# sch.net
KiCad netlist of a schematic drawn in EAGLE
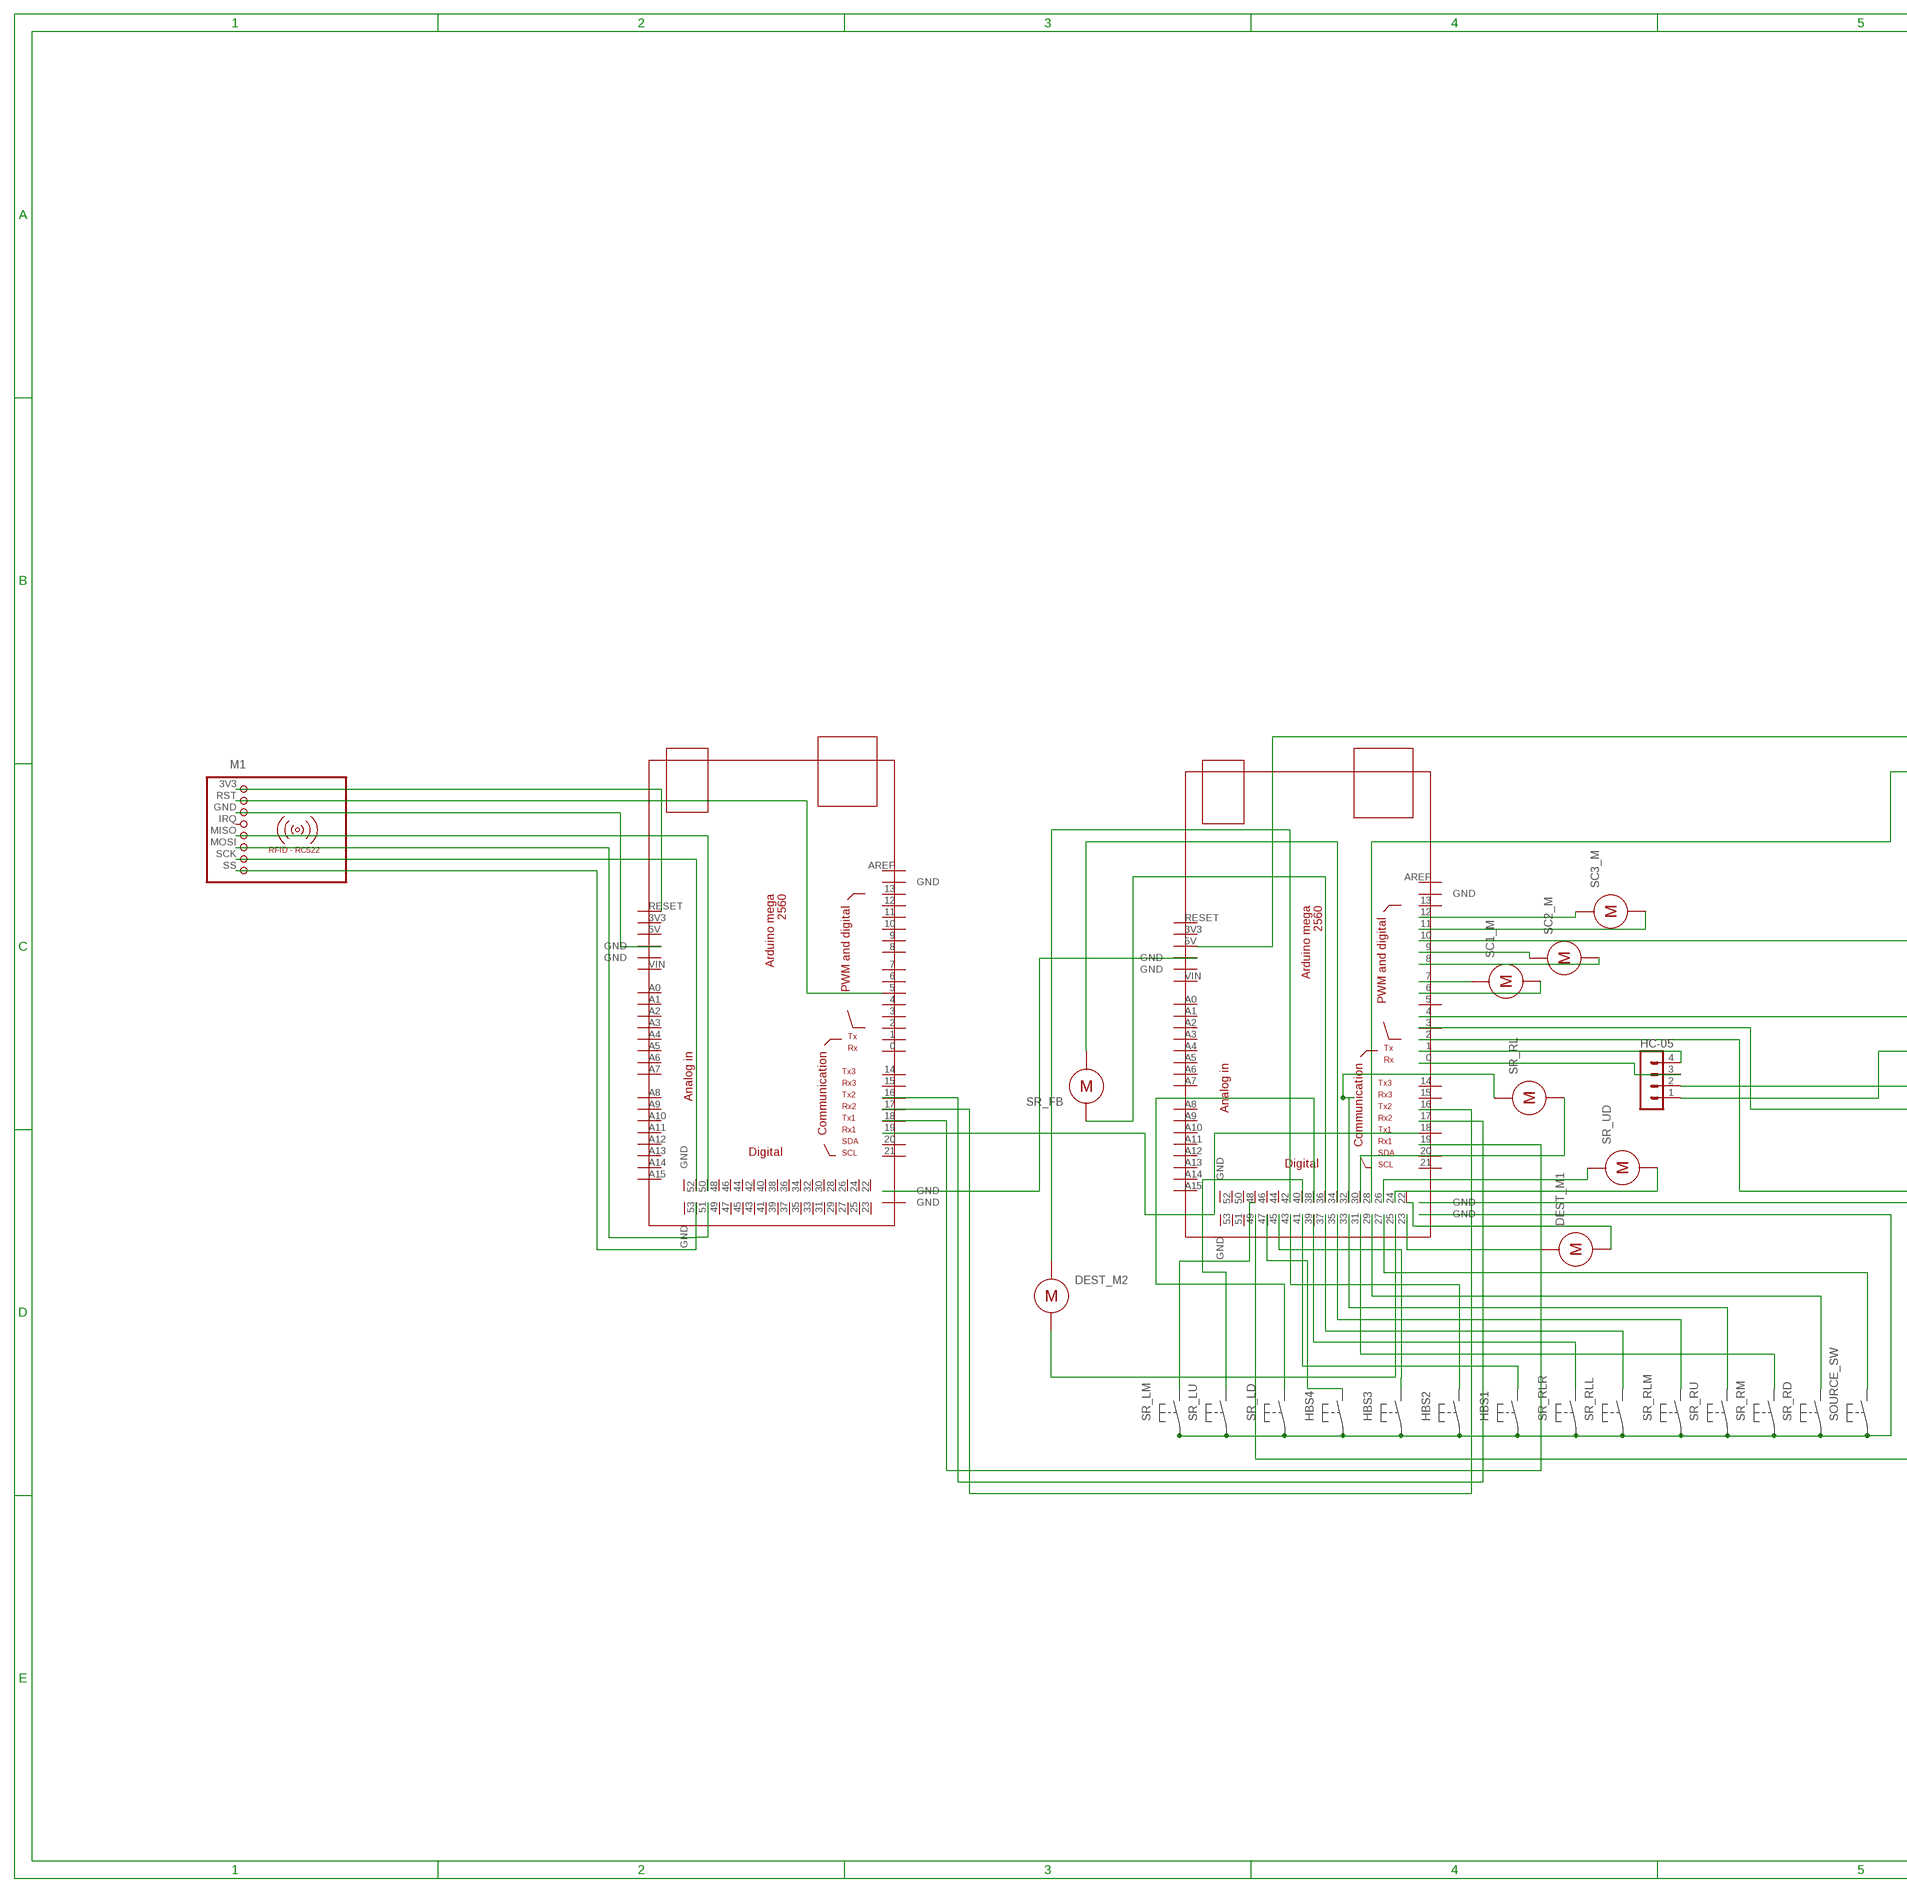
[diagram p0: schematic, sheet 1, part 1 of 2]
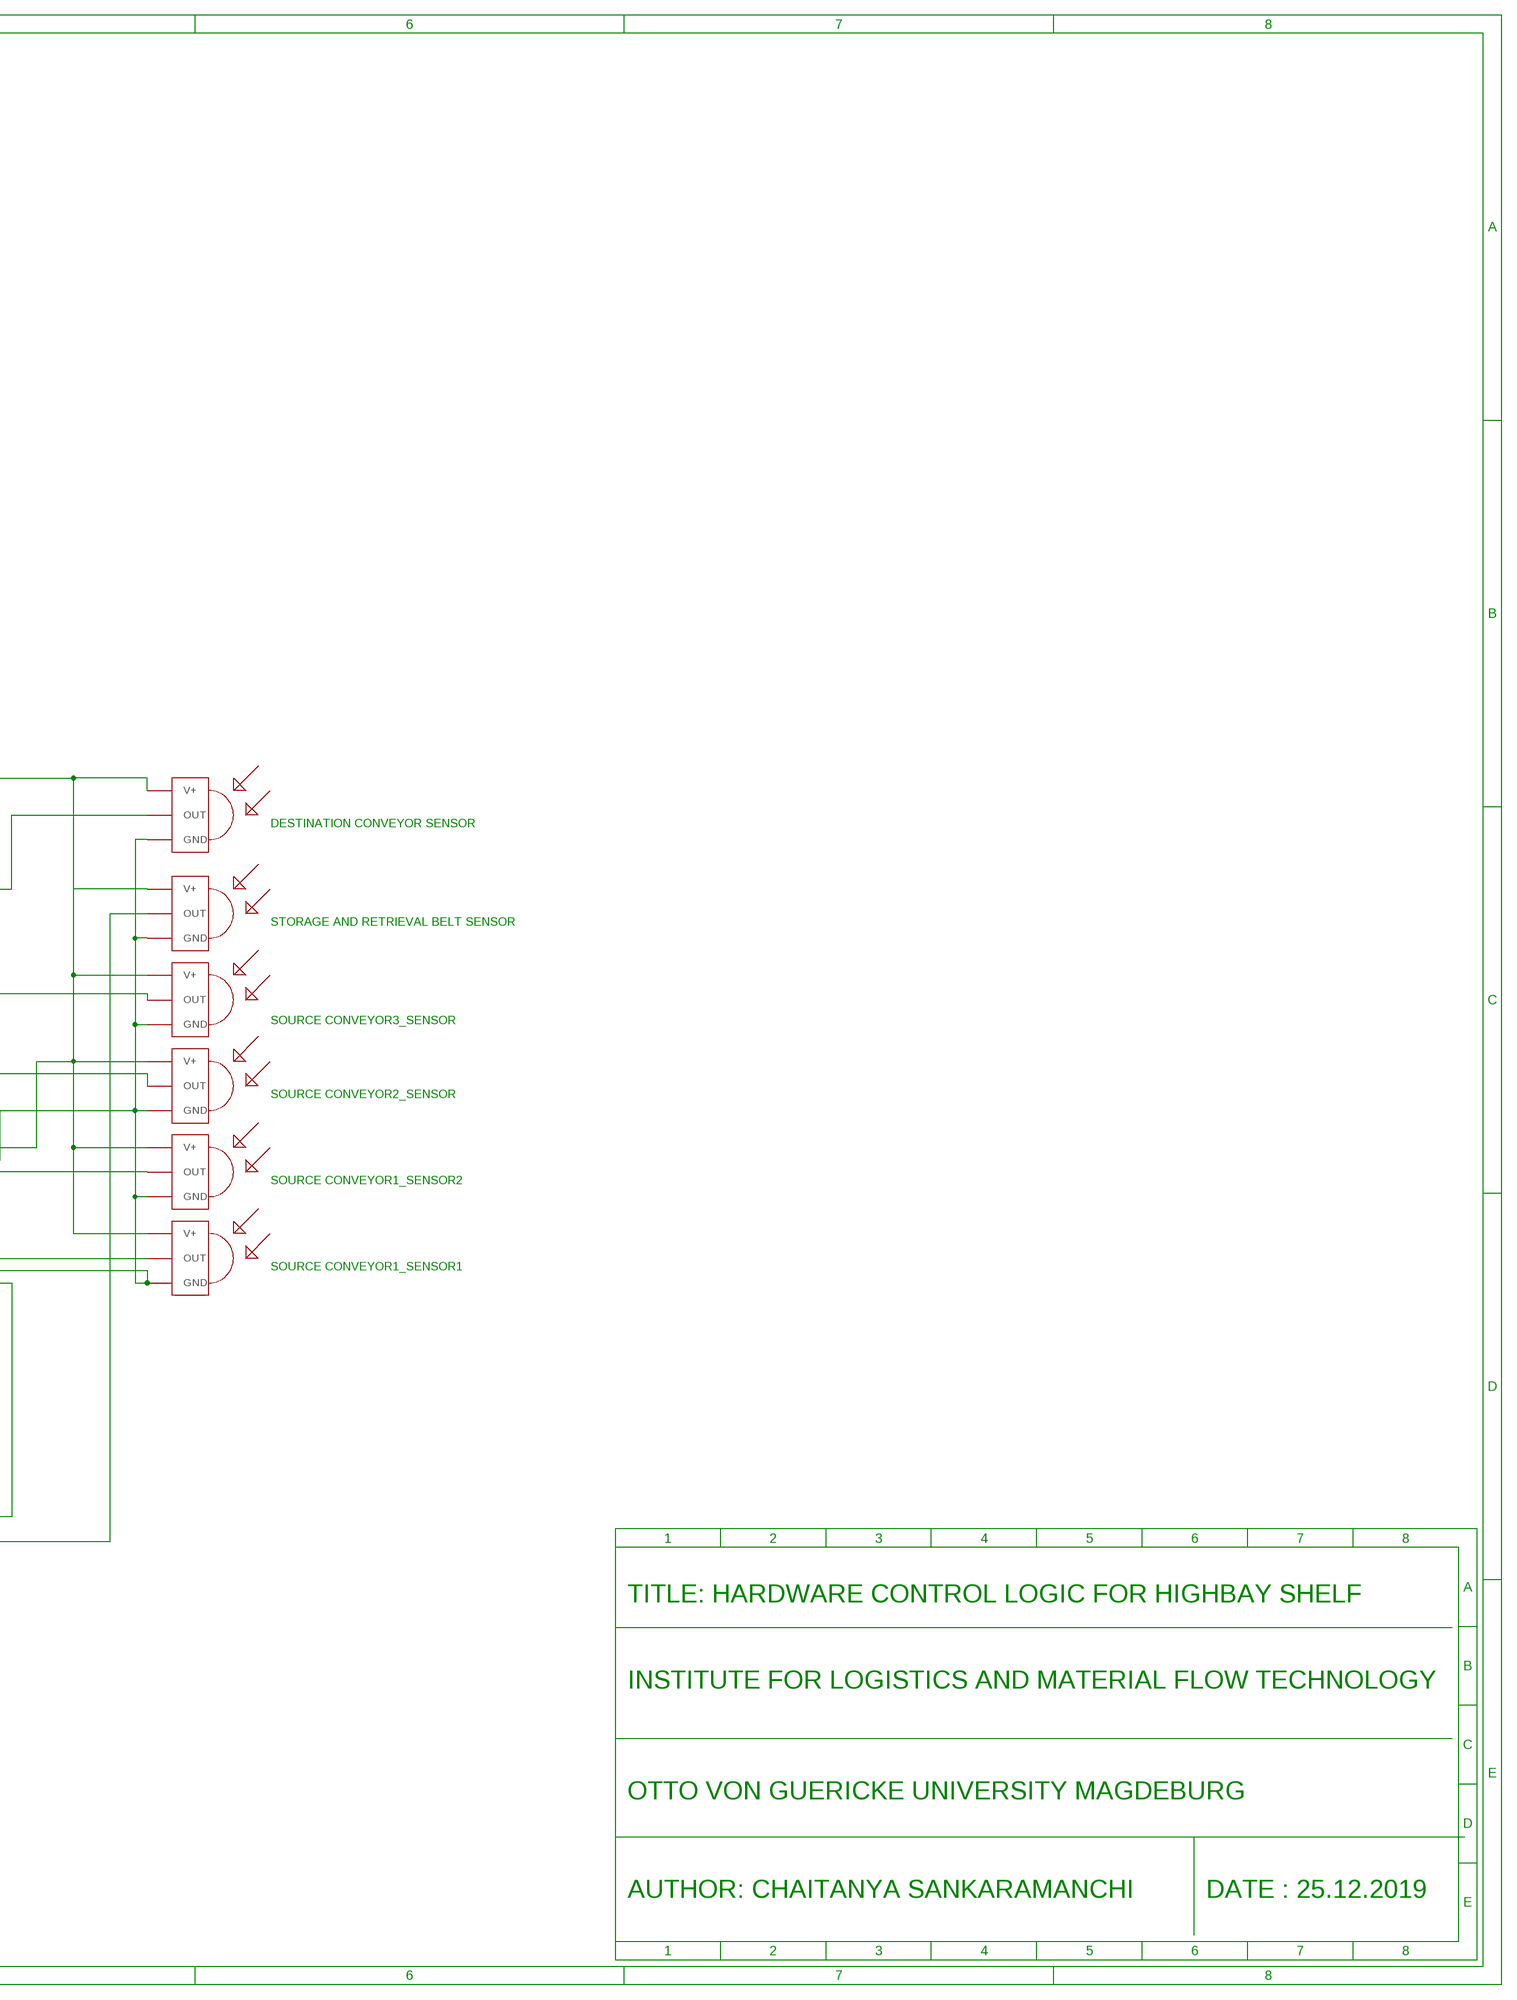
[diagram p1: schematic, sheet 1, part 2 of 2]

(export (version "E")
  (design (tool "Eeschema 10.0.6"))
  (components
    (comp (ref "DEST_M1")
      (value "308-100")
      (footprint "eagle-import:308-100")
      (libsource (lib "eagle-import") (part "308-100"))
    )
    (comp (ref "DEST_M2")
      (value "308-100")
      (footprint "eagle-import:308-100")
      (libsource (lib "eagle-import") (part "308-100"))
    )
    (comp (ref "HC-05")
      (value "MA04-1")
      (footprint "eagle-import:MA04-1")
      (libsource (lib "eagle-import") (part "MA04-1"))
    )
    (comp (ref "M1")
      (value "RFID-RC522")
      (footprint "eagle-import:RFID-RC522")
      (libsource (lib "eagle-import") (part "RFID-RC522"))
    )
    (comp (ref "SC1_M")
      (value "308-100")
      (footprint "eagle-import:308-100")
      (libsource (lib "eagle-import") (part "308-100"))
    )
    (comp (ref "SC1_SENS1")
      (value "TSOP1730")
      (footprint "eagle-import:TSOP17XX")
      (libsource (lib "eagle-import") (part "TSOP1730"))
    )
    (comp (ref "SC1_SENS2")
      (value "TSOP1730")
      (footprint "eagle-import:TSOP17XX")
      (libsource (lib "eagle-import") (part "TSOP1730"))
    )
    (comp (ref "SC2_M")
      (value "308-100")
      (footprint "eagle-import:308-100")
      (libsource (lib "eagle-import") (part "308-100"))
    )
    (comp (ref "SC2_SENS")
      (value "TSOP1730")
      (footprint "eagle-import:TSOP17XX")
      (libsource (lib "eagle-import") (part "TSOP1730"))
    )
    (comp (ref "SC3_M")
      (value "308-100")
      (footprint "eagle-import:308-100")
      (libsource (lib "eagle-import") (part "308-100"))
    )
    (comp (ref "SC3_SENS")
      (value "TSOP1730")
      (footprint "eagle-import:TSOP17XX")
      (libsource (lib "eagle-import") (part "TSOP1730"))
    )
    (comp (ref "SRB_SENS")
      (value "TSOP1730")
      (footprint "eagle-import:TSOP17XX")
      (libsource (lib "eagle-import") (part "TSOP1730"))
    )
    (comp (ref "SRB_SENS1")
      (value "TSOP1730")
      (footprint "eagle-import:TSOP17XX")
      (libsource (lib "eagle-import") (part "TSOP1730"))
    )
    (comp (ref "SR_FB")
      (value "308-100")
      (footprint "eagle-import:308-100")
      (libsource (lib "eagle-import") (part "308-100"))
    )
    (comp (ref "SR_RL")
      (value "308-100")
      (footprint "eagle-import:308-100")
      (libsource (lib "eagle-import") (part "308-100"))
    )
    (comp (ref "SR_UD")
      (value "308-100")
      (footprint "eagle-import:308-100")
      (libsource (lib "eagle-import") (part "308-100"))
    )
    (comp (ref "U$1")
      (value "MEGA_DEVICE")
      (footprint "eagle-import:MEGAOUTLINE")
      (libsource (lib "eagle-import") (part "MEGA_DEVICE"))
    )
    (comp (ref "U$2")
      (value "MEGA_DEVICE")
      (footprint "eagle-import:MEGAOUTLINE")
      (libsource (lib "eagle-import") (part "MEGA_DEVICE"))
    )
  )
  (nets
    (net (code "1") (name "Net-(DEST_M1-PadNEG)") (class "Default")
      (node (ref "DEST_M1") (pin "NEG") (pinfunction "NEG_NEG") (pintype "bidirectional"))
      (node (ref "U$1") (pin "22") (pinfunction "22_22") (pintype "bidirectional"))
    )
    (net (code "2") (name "Net-(DEST_M1-PadPOS)") (class "Default")
      (node (ref "DEST_M1") (pin "POS") (pinfunction "POS_POS") (pintype "bidirectional"))
      (node (ref "U$1") (pin "23") (pinfunction "23_23") (pintype "bidirectional"))
    )
    (net (code "3") (name "Net-(DEST_M2-PadNEG)") (class "Default")
      (node (ref "DEST_M2") (pin "NEG") (pinfunction "NEG_NEG") (pintype "bidirectional"))
      (node (ref "U$1") (pin "25") (pinfunction "25_25") (pintype "bidirectional"))
    )
    (net (code "4") (name "Net-(DEST_M2-PadPOS)") (class "Default")
      (node (ref "DEST_M2") (pin "POS") (pinfunction "POS_POS") (pintype "bidirectional"))
      (node (ref "U$1") (pin "42") (pinfunction "42_42") (pintype "bidirectional"))
    )
    (net (code "5") (name "Net-(HC-05-Pad1)") (class "Default")
      (node (ref "HC-05") (pin "1") (pinfunction "1_1") (pintype "passive"))
      (node (ref "SC1_SENS1") (pin "GND") (pinfunction "GND_GND") (pintype "bidirectional"))
      (node (ref "SC1_SENS2") (pin "GND") (pinfunction "GND_GND") (pintype "bidirectional"))
      (node (ref "SC2_SENS") (pin "GND") (pinfunction "GND_GND") (pintype "bidirectional"))
      (node (ref "SC3_SENS") (pin "GND") (pinfunction "GND_GND") (pintype "bidirectional"))
      (node (ref "SRB_SENS") (pin "GND") (pinfunction "GND_GND") (pintype "bidirectional"))
      (node (ref "SRB_SENS1") (pin "GND") (pinfunction "GND_GND") (pintype "bidirectional"))
      (node (ref "U$1") (pin "GND@4") (pinfunction "GND_GND@4") (pintype "bidirectional"))
    )
    (net (code "6") (name "Net-(HC-05-Pad2)") (class "Default")
      (node (ref "HC-05") (pin "2") (pinfunction "2_2") (pintype "passive"))
      (node (ref "SC1_SENS1") (pin "V+") (pinfunction "V+_V+") (pintype "bidirectional"))
      (node (ref "SC1_SENS2") (pin "V+") (pinfunction "V+_V+") (pintype "bidirectional"))
      (node (ref "SC2_SENS") (pin "V+") (pinfunction "V+_V+") (pintype "bidirectional"))
      (node (ref "SC3_SENS") (pin "V+") (pinfunction "V+_V+") (pintype "bidirectional"))
      (node (ref "SRB_SENS") (pin "V+") (pinfunction "V+_V+") (pintype "bidirectional"))
      (node (ref "SRB_SENS1") (pin "V+") (pinfunction "V+_V+") (pintype "bidirectional"))
      (node (ref "U$1") (pin "5V") (pinfunction "5V_5V") (pintype "bidirectional"))
    )
    (net (code "7") (name "Net-(HC-05-Pad3)") (class "Default")
      (node (ref "HC-05") (pin "3") (pinfunction "3_3") (pintype "passive"))
      (node (ref "U$1") (pin "0") (pinfunction "0_0") (pintype "bidirectional"))
    )
    (net (code "8") (name "Net-(HC-05-Pad4)") (class "Default")
      (node (ref "HC-05") (pin "4") (pinfunction "4_4") (pintype "passive"))
      (node (ref "U$1") (pin "1") (pinfunction "1_1") (pintype "bidirectional"))
    )
    (net (code "9") (name "Net-(M1-1)") (class "Default")
      (node (ref "M1") (pin "3V3") (pinfunction "1_3V3") (pintype "passive"))
      (node (ref "U$2") (pin "RESET") (pinfunction "RESET_RESET") (pintype "bidirectional"))
    )
    (net (code "10") (name "Net-(M1-2)") (class "Default")
      (node (ref "M1") (pin "RST") (pinfunction "2_RST") (pintype "passive"))
      (node (ref "U$2") (pin "5") (pinfunction "5_5") (pintype "bidirectional"))
    )
    (net (code "11") (name "Net-(M1-3)") (class "Default")
      (node (ref "M1") (pin "GND") (pinfunction "3_GND") (pintype "passive"))
      (node (ref "U$2") (pin "GND@2") (pinfunction "GND_GND@2") (pintype "bidirectional"))
    )
    (net (code "12") (name "Net-(M1-5)") (class "Default")
      (node (ref "M1") (pin "MISO") (pinfunction "5_MISO") (pintype "passive"))
      (node (ref "U$2") (pin "50") (pinfunction "50_50") (pintype "bidirectional"))
    )
    (net (code "13") (name "Net-(M1-6)") (class "Default")
      (node (ref "M1") (pin "MOSI") (pinfunction "6_MOSI") (pintype "passive"))
      (node (ref "U$2") (pin "51") (pinfunction "51_51") (pintype "bidirectional"))
    )
    (net (code "14") (name "Net-(M1-7)") (class "Default")
      (node (ref "M1") (pin "SCK") (pinfunction "7_SCK") (pintype "passive"))
      (node (ref "U$2") (pin "52") (pinfunction "52_52") (pintype "bidirectional"))
    )
    (net (code "15") (name "Net-(M1-8)") (class "Default")
      (node (ref "M1") (pin "SS") (pinfunction "8_SS") (pintype "passive"))
      (node (ref "U$2") (pin "53") (pinfunction "53_53") (pintype "bidirectional"))
    )
    (net (code "16") (name "Net-(SC1_M-PadNEG)") (class "Default")
      (node (ref "SC1_M") (pin "NEG") (pinfunction "NEG_NEG") (pintype "bidirectional"))
      (node (ref "U$1") (pin "6") (pinfunction "6_6") (pintype "bidirectional"))
    )
    (net (code "17") (name "Net-(SC1_M-PadPOS)") (class "Default")
      (node (ref "SC1_M") (pin "POS") (pinfunction "POS_POS") (pintype "bidirectional"))
      (node (ref "U$1") (pin "7") (pinfunction "7_7") (pintype "bidirectional"))
    )
    (net (code "18") (name "Net-(SC1_SENS1-PadOUT)") (class "Default")
      (node (ref "SC1_SENS1") (pin "OUT") (pinfunction "OUT_OUT") (pintype "bidirectional"))
      (node (ref "U$1") (pin "2") (pinfunction "2_2") (pintype "bidirectional"))
    )
    (net (code "19") (name "Net-(SC1_SENS2-PadOUT)") (class "Default")
      (node (ref "SC1_SENS2") (pin "OUT") (pinfunction "OUT_OUT") (pintype "bidirectional"))
      (node (ref "U$1") (pin "3") (pinfunction "3_3") (pintype "bidirectional"))
    )
    (net (code "20") (name "Net-(SC2_M-PadNEG)") (class "Default")
      (node (ref "SC2_M") (pin "NEG") (pinfunction "NEG_NEG") (pintype "bidirectional"))
      (node (ref "U$1") (pin "8") (pinfunction "8_8") (pintype "bidirectional"))
    )
    (net (code "21") (name "Net-(SC2_M-PadPOS)") (class "Default")
      (node (ref "SC2_M") (pin "POS") (pinfunction "POS_POS") (pintype "bidirectional"))
      (node (ref "U$1") (pin "9") (pinfunction "9_9") (pintype "bidirectional"))
    )
    (net (code "22") (name "Net-(SC2_SENS-PadOUT)") (class "Default")
      (node (ref "SC2_SENS") (pin "OUT") (pinfunction "OUT_OUT") (pintype "bidirectional"))
      (node (ref "U$1") (pin "4") (pinfunction "4_4") (pintype "bidirectional"))
    )
    (net (code "23") (name "Net-(SC3_M-PadNEG)") (class "Default")
      (node (ref "SC3_M") (pin "NEG") (pinfunction "NEG_NEG") (pintype "bidirectional"))
      (node (ref "U$1") (pin "11") (pinfunction "11_11") (pintype "bidirectional"))
    )
    (net (code "24") (name "Net-(SC3_M-PadPOS)") (class "Default")
      (node (ref "SC3_M") (pin "POS") (pinfunction "POS_POS") (pintype "bidirectional"))
      (node (ref "U$1") (pin "12") (pinfunction "12_12") (pintype "bidirectional"))
    )
    (net (code "25") (name "Net-(SC3_SENS-PadOUT)") (class "Default")
      (node (ref "SC3_SENS") (pin "OUT") (pinfunction "OUT_OUT") (pintype "bidirectional"))
      (node (ref "U$1") (pin "10") (pinfunction "10_10") (pintype "bidirectional"))
    )
    (net (code "26") (name "Net-(SRB_SENS-PadOUT)") (class "Default")
      (node (ref "SRB_SENS") (pin "OUT") (pinfunction "OUT_OUT") (pintype "bidirectional"))
      (node (ref "U$1") (pin "49") (pinfunction "49_49") (pintype "bidirectional"))
    )
    (net (code "27") (name "Net-(SRB_SENS1-PadOUT)") (class "Default")
      (node (ref "SRB_SENS1") (pin "OUT") (pinfunction "OUT_OUT") (pintype "bidirectional"))
      (node (ref "U$1") (pin "28") (pinfunction "28_28") (pintype "bidirectional"))
    )
    (net (code "28") (name "Net-(SR_FB-PadNEG)") (class "Default")
      (node (ref "SR_FB") (pin "NEG") (pinfunction "NEG_NEG") (pintype "bidirectional"))
      (node (ref "U$1") (pin "34") (pinfunction "34_34") (pintype "bidirectional"))
    )
    (net (code "29") (name "Net-(SR_FB-PadPOS)") (class "Default")
      (node (ref "SR_FB") (pin "POS") (pinfunction "POS_POS") (pintype "bidirectional"))
      (node (ref "U$1") (pin "36") (pinfunction "36_36") (pintype "bidirectional"))
    )
    (net (code "30") (name "Net-(SR_RL-PadNEG)") (class "Default")
      (node (ref "SR_RL") (pin "NEG") (pinfunction "NEG_NEG") (pintype "bidirectional"))
      (node (ref "U$1") (pin "20") (pinfunction "20_20") (pintype "bidirectional"))
      (node (ref "U$1") (pin "30") (pinfunction "30_30") (pintype "bidirectional"))
    )
    (net (code "31") (name "Net-(SR_UD-PadNEG)") (class "Default")
      (node (ref "SR_UD") (pin "NEG") (pinfunction "NEG_NEG") (pintype "bidirectional"))
      (node (ref "U$1") (pin "24") (pinfunction "24_24") (pintype "bidirectional"))
    )
    (net (code "32") (name "Net-(SR_UD-PadPOS)") (class "Default")
      (node (ref "SR_UD") (pin "POS") (pinfunction "POS_POS") (pintype "bidirectional"))
      (node (ref "U$1") (pin "26") (pinfunction "26_26") (pintype "bidirectional"))
    )
    (net (code "33") (name "Net-(U$1-GND-PadGND@2)") (class "Default")
      (node (ref "U$1") (pin "GND@2") (pinfunction "GND_GND@2") (pintype "bidirectional"))
      (node (ref "U$2") (pin "GND@4") (pinfunction "GND_GND@4") (pintype "bidirectional"))
    )
    (net (code "34") (name "Net-(U$1-Pad16)") (class "Default")
      (node (ref "U$1") (pin "16") (pinfunction "16_16") (pintype "bidirectional"))
      (node (ref "U$2") (pin "17") (pinfunction "17_17") (pintype "bidirectional"))
    )
    (net (code "35") (name "Net-(U$1-Pad17)") (class "Default")
      (node (ref "U$1") (pin "17") (pinfunction "17_17") (pintype "bidirectional"))
      (node (ref "U$2") (pin "16") (pinfunction "16_16") (pintype "bidirectional"))
    )
    (net (code "36") (name "Net-(U$1-Pad18)") (class "Default")
      (node (ref "U$1") (pin "18") (pinfunction "18_18") (pintype "bidirectional"))
      (node (ref "U$2") (pin "19") (pinfunction "19_19") (pintype "bidirectional"))
    )
    (net (code "37") (name "Net-(U$1-Pad19)") (class "Default")
      (node (ref "U$1") (pin "19") (pinfunction "19_19") (pintype "bidirectional"))
      (node (ref "U$2") (pin "18") (pinfunction "18_18") (pintype "bidirectional"))
    )
    (net (code "38") (name "unconnected-(M1-4-PadIRQ)") (class "Default")
      (node (ref "M1") (pin "IRQ") (pinfunction "4_IRQ") (pintype "passive"))
    )
    (net (code "39") (name "unconnected-(SR_RL-PadPOS)") (class "Default")
      (node (ref "SR_RL") (pin "POS") (pinfunction "POS_POS") (pintype "bidirectional"))
    )
    (net (code "40") (name "unconnected-(U$1-GND-PadGND@1)") (class "Default")
      (node (ref "U$1") (pin "GND@1") (pinfunction "GND_GND@1") (pintype "bidirectional"))
    )
    (net (code "41") (name "unconnected-(U$1-GND-PadGND@3)") (class "Default")
      (node (ref "U$1") (pin "GND@3") (pinfunction "GND_GND@3") (pintype "bidirectional"))
    )
    (net (code "42") (name "unconnected-(U$1-GND-PadGND@5)") (class "Default")
      (node (ref "U$1") (pin "GND@5") (pinfunction "GND_GND@5") (pintype "bidirectional"))
    )
    (net (code "43") (name "unconnected-(U$1-GND-PadGND@6)") (class "Default")
      (node (ref "U$1") (pin "GND@6") (pinfunction "GND_GND@6") (pintype "bidirectional"))
    )
    (net (code "44") (name "unconnected-(U$1-GND-PadGND@7)") (class "Default")
      (node (ref "U$1") (pin "GND@7") (pinfunction "GND_GND@7") (pintype "bidirectional"))
    )
    (net (code "45") (name "unconnected-(U$1-Pad3V3)") (class "Default")
      (node (ref "U$1") (pin "3V3") (pinfunction "3V3_3V3") (pintype "bidirectional"))
    )
    (net (code "46") (name "unconnected-(U$1-Pad5)") (class "Default")
      (node (ref "U$1") (pin "5") (pinfunction "5_5") (pintype "bidirectional"))
    )
    (net (code "47") (name "unconnected-(U$1-Pad13)") (class "Default")
      (node (ref "U$1") (pin "13") (pinfunction "13_13") (pintype "bidirectional"))
    )
    (net (code "48") (name "unconnected-(U$1-Pad14)") (class "Default")
      (node (ref "U$1") (pin "14") (pinfunction "14_14") (pintype "bidirectional"))
    )
    (net (code "49") (name "unconnected-(U$1-Pad15)") (class "Default")
      (node (ref "U$1") (pin "15") (pinfunction "15_15") (pintype "bidirectional"))
    )
    (net (code "50") (name "unconnected-(U$1-Pad21)") (class "Default")
      (node (ref "U$1") (pin "21") (pinfunction "21_21") (pintype "bidirectional"))
    )
    (net (code "51") (name "unconnected-(U$1-Pad27)") (class "Default")
      (node (ref "U$1") (pin "27") (pinfunction "27_27") (pintype "bidirectional"))
    )
    (net (code "52") (name "unconnected-(U$1-Pad29)") (class "Default")
      (node (ref "U$1") (pin "29") (pinfunction "29_29") (pintype "bidirectional"))
    )
    (net (code "53") (name "unconnected-(U$1-Pad31)") (class "Default")
      (node (ref "U$1") (pin "31") (pinfunction "31_31") (pintype "bidirectional"))
    )
    (net (code "54") (name "unconnected-(U$1-Pad32)") (class "Default")
      (node (ref "U$1") (pin "32") (pinfunction "32_32") (pintype "bidirectional"))
    )
    (net (code "55") (name "unconnected-(U$1-Pad33)") (class "Default")
      (node (ref "U$1") (pin "33") (pinfunction "33_33") (pintype "bidirectional"))
    )
    (net (code "56") (name "unconnected-(U$1-Pad35)") (class "Default")
      (node (ref "U$1") (pin "35") (pinfunction "35_35") (pintype "bidirectional"))
    )
    (net (code "57") (name "unconnected-(U$1-Pad37)") (class "Default")
      (node (ref "U$1") (pin "37") (pinfunction "37_37") (pintype "bidirectional"))
    )
    (net (code "58") (name "unconnected-(U$1-Pad38)") (class "Default")
      (node (ref "U$1") (pin "38") (pinfunction "38_38") (pintype "bidirectional"))
    )
    (net (code "59") (name "unconnected-(U$1-Pad39)") (class "Default")
      (node (ref "U$1") (pin "39") (pinfunction "39_39") (pintype "bidirectional"))
    )
    (net (code "60") (name "unconnected-(U$1-Pad40)") (class "Default")
      (node (ref "U$1") (pin "40") (pinfunction "40_40") (pintype "bidirectional"))
    )
    (net (code "61") (name "unconnected-(U$1-Pad41)") (class "Default")
      (node (ref "U$1") (pin "41") (pinfunction "41_41") (pintype "bidirectional"))
    )
    (net (code "62") (name "unconnected-(U$1-Pad43)") (class "Default")
      (node (ref "U$1") (pin "43") (pinfunction "43_43") (pintype "bidirectional"))
    )
    (net (code "63") (name "unconnected-(U$1-Pad44)") (class "Default")
      (node (ref "U$1") (pin "44") (pinfunction "44_44") (pintype "bidirectional"))
    )
    (net (code "64") (name "unconnected-(U$1-Pad45)") (class "Default")
      (node (ref "U$1") (pin "45") (pinfunction "45_45") (pintype "bidirectional"))
    )
    (net (code "65") (name "unconnected-(U$1-Pad46)") (class "Default")
      (node (ref "U$1") (pin "46") (pinfunction "46_46") (pintype "bidirectional"))
    )
    (net (code "66") (name "unconnected-(U$1-Pad47)") (class "Default")
      (node (ref "U$1") (pin "47") (pinfunction "47_47") (pintype "bidirectional"))
    )
    (net (code "67") (name "unconnected-(U$1-Pad48)") (class "Default")
      (node (ref "U$1") (pin "48") (pinfunction "48_48") (pintype "bidirectional"))
    )
    (net (code "68") (name "unconnected-(U$1-Pad50)") (class "Default")
      (node (ref "U$1") (pin "50") (pinfunction "50_50") (pintype "bidirectional"))
    )
    (net (code "69") (name "unconnected-(U$1-Pad51)") (class "Default")
      (node (ref "U$1") (pin "51") (pinfunction "51_51") (pintype "bidirectional"))
    )
    (net (code "70") (name "unconnected-(U$1-Pad52)") (class "Default")
      (node (ref "U$1") (pin "52") (pinfunction "52_52") (pintype "bidirectional"))
    )
    (net (code "71") (name "unconnected-(U$1-Pad53)") (class "Default")
      (node (ref "U$1") (pin "53") (pinfunction "53_53") (pintype "bidirectional"))
    )
    (net (code "72") (name "unconnected-(U$1-PadA0)") (class "Default")
      (node (ref "U$1") (pin "A0") (pinfunction "A0_A0") (pintype "bidirectional"))
    )
    (net (code "73") (name "unconnected-(U$1-PadA1)") (class "Default")
      (node (ref "U$1") (pin "A1") (pinfunction "A1_A1") (pintype "bidirectional"))
    )
    (net (code "74") (name "unconnected-(U$1-PadA2)") (class "Default")
      (node (ref "U$1") (pin "A2") (pinfunction "A2_A2") (pintype "bidirectional"))
    )
    (net (code "75") (name "unconnected-(U$1-PadA3)") (class "Default")
      (node (ref "U$1") (pin "A3") (pinfunction "A3_A3") (pintype "bidirectional"))
    )
    (net (code "76") (name "unconnected-(U$1-PadA4)") (class "Default")
      (node (ref "U$1") (pin "A4") (pinfunction "A4_A4") (pintype "bidirectional"))
    )
    (net (code "77") (name "unconnected-(U$1-PadA5)") (class "Default")
      (node (ref "U$1") (pin "A5") (pinfunction "A5_A5") (pintype "bidirectional"))
    )
    (net (code "78") (name "unconnected-(U$1-PadA6)") (class "Default")
      (node (ref "U$1") (pin "A6") (pinfunction "A6_A6") (pintype "bidirectional"))
    )
    (net (code "79") (name "unconnected-(U$1-PadA7)") (class "Default")
      (node (ref "U$1") (pin "A7") (pinfunction "A7_A7") (pintype "bidirectional"))
    )
    (net (code "80") (name "unconnected-(U$1-PadA8)") (class "Default")
      (node (ref "U$1") (pin "A8") (pinfunction "A8_A8") (pintype "bidirectional"))
    )
    (net (code "81") (name "unconnected-(U$1-PadA9)") (class "Default")
      (node (ref "U$1") (pin "A9") (pinfunction "A9_A9") (pintype "bidirectional"))
    )
    (net (code "82") (name "unconnected-(U$1-PadA10)") (class "Default")
      (node (ref "U$1") (pin "A10") (pinfunction "A10_A10") (pintype "bidirectional"))
    )
    (net (code "83") (name "unconnected-(U$1-PadA11)") (class "Default")
      (node (ref "U$1") (pin "A11") (pinfunction "A11_A11") (pintype "bidirectional"))
    )
    (net (code "84") (name "unconnected-(U$1-PadA12)") (class "Default")
      (node (ref "U$1") (pin "A12") (pinfunction "A12_A12") (pintype "bidirectional"))
    )
    (net (code "85") (name "unconnected-(U$1-PadA13)") (class "Default")
      (node (ref "U$1") (pin "A13") (pinfunction "A13_A13") (pintype "bidirectional"))
    )
    (net (code "86") (name "unconnected-(U$1-PadA14)") (class "Default")
      (node (ref "U$1") (pin "A14") (pinfunction "A14_A14") (pintype "bidirectional"))
    )
    (net (code "87") (name "unconnected-(U$1-PadA15)") (class "Default")
      (node (ref "U$1") (pin "A15") (pinfunction "A15_A15") (pintype "bidirectional"))
    )
    (net (code "88") (name "unconnected-(U$1-PadAREF)") (class "Default")
      (node (ref "U$1") (pin "AREF") (pinfunction "AREF_AREF") (pintype "bidirectional"))
    )
    (net (code "89") (name "unconnected-(U$1-PadRESET)") (class "Default")
      (node (ref "U$1") (pin "RESET") (pinfunction "RESET_RESET") (pintype "bidirectional"))
    )
    (net (code "90") (name "unconnected-(U$1-PadVIN)") (class "Default")
      (node (ref "U$1") (pin "VIN") (pinfunction "VIN_VIN") (pintype "bidirectional"))
    )
    (net (code "91") (name "unconnected-(U$2-GND-PadGND@1)") (class "Default")
      (node (ref "U$2") (pin "GND@1") (pinfunction "GND_GND@1") (pintype "bidirectional"))
    )
    (net (code "92") (name "unconnected-(U$2-GND-PadGND@3)") (class "Default")
      (node (ref "U$2") (pin "GND@3") (pinfunction "GND_GND@3") (pintype "bidirectional"))
    )
    (net (code "93") (name "unconnected-(U$2-GND-PadGND@5)") (class "Default")
      (node (ref "U$2") (pin "GND@5") (pinfunction "GND_GND@5") (pintype "bidirectional"))
    )
    (net (code "94") (name "unconnected-(U$2-GND-PadGND@6)") (class "Default")
      (node (ref "U$2") (pin "GND@6") (pinfunction "GND_GND@6") (pintype "bidirectional"))
    )
    (net (code "95") (name "unconnected-(U$2-GND-PadGND@7)") (class "Default")
      (node (ref "U$2") (pin "GND@7") (pinfunction "GND_GND@7") (pintype "bidirectional"))
    )
    (net (code "96") (name "unconnected-(U$2-Pad0)") (class "Default")
      (node (ref "U$2") (pin "0") (pinfunction "0_0") (pintype "bidirectional"))
    )
    (net (code "97") (name "unconnected-(U$2-Pad1)") (class "Default")
      (node (ref "U$2") (pin "1") (pinfunction "1_1") (pintype "bidirectional"))
    )
    (net (code "98") (name "unconnected-(U$2-Pad2)") (class "Default")
      (node (ref "U$2") (pin "2") (pinfunction "2_2") (pintype "bidirectional"))
    )
    (net (code "99") (name "unconnected-(U$2-Pad3)") (class "Default")
      (node (ref "U$2") (pin "3") (pinfunction "3_3") (pintype "bidirectional"))
    )
    (net (code "100") (name "unconnected-(U$2-Pad3V3)") (class "Default")
      (node (ref "U$2") (pin "3V3") (pinfunction "3V3_3V3") (pintype "bidirectional"))
    )
    (net (code "101") (name "unconnected-(U$2-Pad4)") (class "Default")
      (node (ref "U$2") (pin "4") (pinfunction "4_4") (pintype "bidirectional"))
    )
    (net (code "102") (name "unconnected-(U$2-Pad5V)") (class "Default")
      (node (ref "U$2") (pin "5V") (pinfunction "5V_5V") (pintype "bidirectional"))
    )
    (net (code "103") (name "unconnected-(U$2-Pad6)") (class "Default")
      (node (ref "U$2") (pin "6") (pinfunction "6_6") (pintype "bidirectional"))
    )
    (net (code "104") (name "unconnected-(U$2-Pad7)") (class "Default")
      (node (ref "U$2") (pin "7") (pinfunction "7_7") (pintype "bidirectional"))
    )
    (net (code "105") (name "unconnected-(U$2-Pad8)") (class "Default")
      (node (ref "U$2") (pin "8") (pinfunction "8_8") (pintype "bidirectional"))
    )
    (net (code "106") (name "unconnected-(U$2-Pad9)") (class "Default")
      (node (ref "U$2") (pin "9") (pinfunction "9_9") (pintype "bidirectional"))
    )
    (net (code "107") (name "unconnected-(U$2-Pad10)") (class "Default")
      (node (ref "U$2") (pin "10") (pinfunction "10_10") (pintype "bidirectional"))
    )
    (net (code "108") (name "unconnected-(U$2-Pad11)") (class "Default")
      (node (ref "U$2") (pin "11") (pinfunction "11_11") (pintype "bidirectional"))
    )
    (net (code "109") (name "unconnected-(U$2-Pad12)") (class "Default")
      (node (ref "U$2") (pin "12") (pinfunction "12_12") (pintype "bidirectional"))
    )
    (net (code "110") (name "unconnected-(U$2-Pad13)") (class "Default")
      (node (ref "U$2") (pin "13") (pinfunction "13_13") (pintype "bidirectional"))
    )
    (net (code "111") (name "unconnected-(U$2-Pad14)") (class "Default")
      (node (ref "U$2") (pin "14") (pinfunction "14_14") (pintype "bidirectional"))
    )
    (net (code "112") (name "unconnected-(U$2-Pad15)") (class "Default")
      (node (ref "U$2") (pin "15") (pinfunction "15_15") (pintype "bidirectional"))
    )
    (net (code "113") (name "unconnected-(U$2-Pad20)") (class "Default")
      (node (ref "U$2") (pin "20") (pinfunction "20_20") (pintype "bidirectional"))
    )
    (net (code "114") (name "unconnected-(U$2-Pad21)") (class "Default")
      (node (ref "U$2") (pin "21") (pinfunction "21_21") (pintype "bidirectional"))
    )
    (net (code "115") (name "unconnected-(U$2-Pad22)") (class "Default")
      (node (ref "U$2") (pin "22") (pinfunction "22_22") (pintype "bidirectional"))
    )
    (net (code "116") (name "unconnected-(U$2-Pad23)") (class "Default")
      (node (ref "U$2") (pin "23") (pinfunction "23_23") (pintype "bidirectional"))
    )
    (net (code "117") (name "unconnected-(U$2-Pad24)") (class "Default")
      (node (ref "U$2") (pin "24") (pinfunction "24_24") (pintype "bidirectional"))
    )
    (net (code "118") (name "unconnected-(U$2-Pad25)") (class "Default")
      (node (ref "U$2") (pin "25") (pinfunction "25_25") (pintype "bidirectional"))
    )
    (net (code "119") (name "unconnected-(U$2-Pad26)") (class "Default")
      (node (ref "U$2") (pin "26") (pinfunction "26_26") (pintype "bidirectional"))
    )
    (net (code "120") (name "unconnected-(U$2-Pad27)") (class "Default")
      (node (ref "U$2") (pin "27") (pinfunction "27_27") (pintype "bidirectional"))
    )
    (net (code "121") (name "unconnected-(U$2-Pad28)") (class "Default")
      (node (ref "U$2") (pin "28") (pinfunction "28_28") (pintype "bidirectional"))
    )
    (net (code "122") (name "unconnected-(U$2-Pad29)") (class "Default")
      (node (ref "U$2") (pin "29") (pinfunction "29_29") (pintype "bidirectional"))
    )
    (net (code "123") (name "unconnected-(U$2-Pad30)") (class "Default")
      (node (ref "U$2") (pin "30") (pinfunction "30_30") (pintype "bidirectional"))
    )
    (net (code "124") (name "unconnected-(U$2-Pad31)") (class "Default")
      (node (ref "U$2") (pin "31") (pinfunction "31_31") (pintype "bidirectional"))
    )
    (net (code "125") (name "unconnected-(U$2-Pad32)") (class "Default")
      (node (ref "U$2") (pin "32") (pinfunction "32_32") (pintype "bidirectional"))
    )
    (net (code "126") (name "unconnected-(U$2-Pad33)") (class "Default")
      (node (ref "U$2") (pin "33") (pinfunction "33_33") (pintype "bidirectional"))
    )
    (net (code "127") (name "unconnected-(U$2-Pad34)") (class "Default")
      (node (ref "U$2") (pin "34") (pinfunction "34_34") (pintype "bidirectional"))
    )
    (net (code "128") (name "unconnected-(U$2-Pad35)") (class "Default")
      (node (ref "U$2") (pin "35") (pinfunction "35_35") (pintype "bidirectional"))
    )
    (net (code "129") (name "unconnected-(U$2-Pad36)") (class "Default")
      (node (ref "U$2") (pin "36") (pinfunction "36_36") (pintype "bidirectional"))
    )
    (net (code "130") (name "unconnected-(U$2-Pad37)") (class "Default")
      (node (ref "U$2") (pin "37") (pinfunction "37_37") (pintype "bidirectional"))
    )
    (net (code "131") (name "unconnected-(U$2-Pad38)") (class "Default")
      (node (ref "U$2") (pin "38") (pinfunction "38_38") (pintype "bidirectional"))
    )
    (net (code "132") (name "unconnected-(U$2-Pad39)") (class "Default")
      (node (ref "U$2") (pin "39") (pinfunction "39_39") (pintype "bidirectional"))
    )
    (net (code "133") (name "unconnected-(U$2-Pad40)") (class "Default")
      (node (ref "U$2") (pin "40") (pinfunction "40_40") (pintype "bidirectional"))
    )
    (net (code "134") (name "unconnected-(U$2-Pad41)") (class "Default")
      (node (ref "U$2") (pin "41") (pinfunction "41_41") (pintype "bidirectional"))
    )
    (net (code "135") (name "unconnected-(U$2-Pad42)") (class "Default")
      (node (ref "U$2") (pin "42") (pinfunction "42_42") (pintype "bidirectional"))
    )
    (net (code "136") (name "unconnected-(U$2-Pad43)") (class "Default")
      (node (ref "U$2") (pin "43") (pinfunction "43_43") (pintype "bidirectional"))
    )
    (net (code "137") (name "unconnected-(U$2-Pad44)") (class "Default")
      (node (ref "U$2") (pin "44") (pinfunction "44_44") (pintype "bidirectional"))
    )
    (net (code "138") (name "unconnected-(U$2-Pad45)") (class "Default")
      (node (ref "U$2") (pin "45") (pinfunction "45_45") (pintype "bidirectional"))
    )
    (net (code "139") (name "unconnected-(U$2-Pad46)") (class "Default")
      (node (ref "U$2") (pin "46") (pinfunction "46_46") (pintype "bidirectional"))
    )
    (net (code "140") (name "unconnected-(U$2-Pad47)") (class "Default")
      (node (ref "U$2") (pin "47") (pinfunction "47_47") (pintype "bidirectional"))
    )
    (net (code "141") (name "unconnected-(U$2-Pad48)") (class "Default")
      (node (ref "U$2") (pin "48") (pinfunction "48_48") (pintype "bidirectional"))
    )
    (net (code "142") (name "unconnected-(U$2-Pad49)") (class "Default")
      (node (ref "U$2") (pin "49") (pinfunction "49_49") (pintype "bidirectional"))
    )
    (net (code "143") (name "unconnected-(U$2-PadA0)") (class "Default")
      (node (ref "U$2") (pin "A0") (pinfunction "A0_A0") (pintype "bidirectional"))
    )
    (net (code "144") (name "unconnected-(U$2-PadA1)") (class "Default")
      (node (ref "U$2") (pin "A1") (pinfunction "A1_A1") (pintype "bidirectional"))
    )
    (net (code "145") (name "unconnected-(U$2-PadA2)") (class "Default")
      (node (ref "U$2") (pin "A2") (pinfunction "A2_A2") (pintype "bidirectional"))
    )
    (net (code "146") (name "unconnected-(U$2-PadA3)") (class "Default")
      (node (ref "U$2") (pin "A3") (pinfunction "A3_A3") (pintype "bidirectional"))
    )
    (net (code "147") (name "unconnected-(U$2-PadA4)") (class "Default")
      (node (ref "U$2") (pin "A4") (pinfunction "A4_A4") (pintype "bidirectional"))
    )
    (net (code "148") (name "unconnected-(U$2-PadA5)") (class "Default")
      (node (ref "U$2") (pin "A5") (pinfunction "A5_A5") (pintype "bidirectional"))
    )
    (net (code "149") (name "unconnected-(U$2-PadA6)") (class "Default")
      (node (ref "U$2") (pin "A6") (pinfunction "A6_A6") (pintype "bidirectional"))
    )
    (net (code "150") (name "unconnected-(U$2-PadA7)") (class "Default")
      (node (ref "U$2") (pin "A7") (pinfunction "A7_A7") (pintype "bidirectional"))
    )
    (net (code "151") (name "unconnected-(U$2-PadA8)") (class "Default")
      (node (ref "U$2") (pin "A8") (pinfunction "A8_A8") (pintype "bidirectional"))
    )
    (net (code "152") (name "unconnected-(U$2-PadA9)") (class "Default")
      (node (ref "U$2") (pin "A9") (pinfunction "A9_A9") (pintype "bidirectional"))
    )
    (net (code "153") (name "unconnected-(U$2-PadA10)") (class "Default")
      (node (ref "U$2") (pin "A10") (pinfunction "A10_A10") (pintype "bidirectional"))
    )
    (net (code "154") (name "unconnected-(U$2-PadA11)") (class "Default")
      (node (ref "U$2") (pin "A11") (pinfunction "A11_A11") (pintype "bidirectional"))
    )
    (net (code "155") (name "unconnected-(U$2-PadA12)") (class "Default")
      (node (ref "U$2") (pin "A12") (pinfunction "A12_A12") (pintype "bidirectional"))
    )
    (net (code "156") (name "unconnected-(U$2-PadA13)") (class "Default")
      (node (ref "U$2") (pin "A13") (pinfunction "A13_A13") (pintype "bidirectional"))
    )
    (net (code "157") (name "unconnected-(U$2-PadA14)") (class "Default")
      (node (ref "U$2") (pin "A14") (pinfunction "A14_A14") (pintype "bidirectional"))
    )
    (net (code "158") (name "unconnected-(U$2-PadA15)") (class "Default")
      (node (ref "U$2") (pin "A15") (pinfunction "A15_A15") (pintype "bidirectional"))
    )
    (net (code "159") (name "unconnected-(U$2-PadAREF)") (class "Default")
      (node (ref "U$2") (pin "AREF") (pinfunction "AREF_AREF") (pintype "bidirectional"))
    )
    (net (code "160") (name "unconnected-(U$2-PadVIN)") (class "Default")
      (node (ref "U$2") (pin "VIN") (pinfunction "VIN_VIN") (pintype "bidirectional"))
    )
  )
)
